# moduloTransceptorRF.net
KiCad netlist of a schematic drawn in Altium Designer
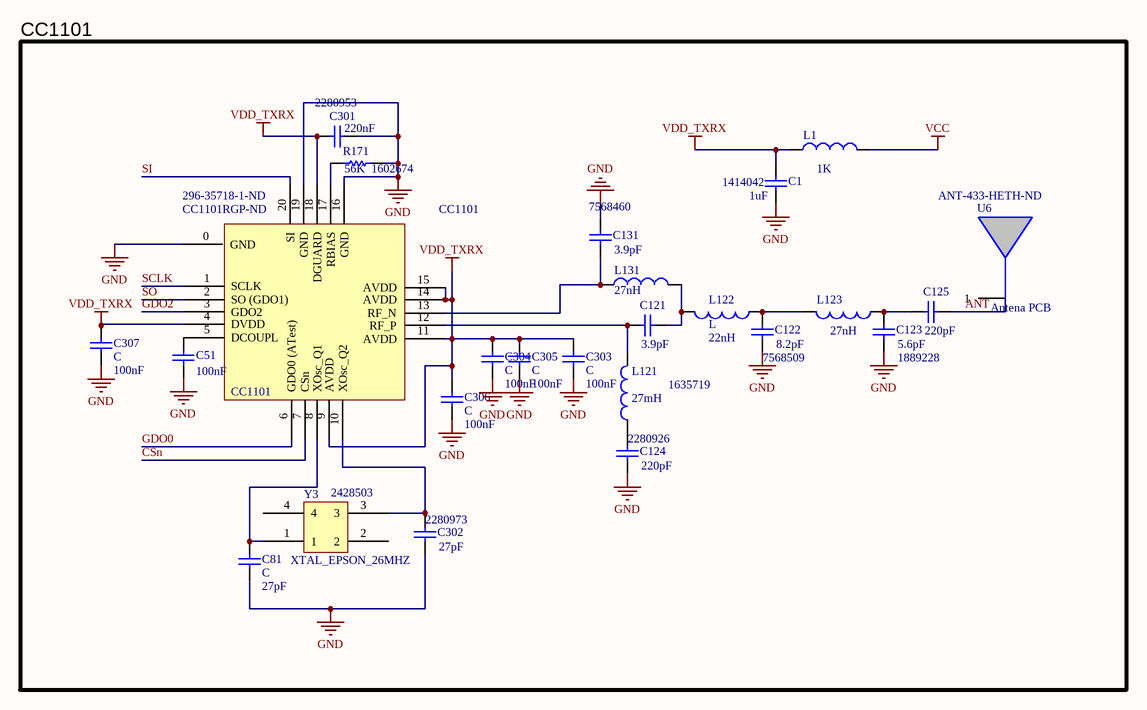
[diagram p0: moduloTransceptorRF.SchDoc]

(export (version "E")
  (design (tool "Eeschema 10.0.6"))
  (components
    (comp (ref "C1")
      (value "1uF")
      (footprint "0805 CAP")
      (description "Capacitor")
      (fields
        (field (name "MANUFACTURER") "Generic Components")
        (field (name "SUPPLIER PART NUMBER 3") "1414042")
        (field (name "Comment") "C")
        (field (name "PUBLISHER") "Altium Hobart Technology Centre")
      )
      (libsource (lib "LSI") (part "C"))
    )
    (comp (ref "C51")
      (value "100nF")
      (footprint "0805 CAP")
      (description "Capacitor")
      (fields
        (field (name "MANUFACTURER") "Generic Components")
        (field (name "Comment") "C")
        (field (name "PUBLISHER") "Altium Hobart Technology Centre")
      )
      (libsource (lib "LSI") (part "C"))
    )
    (comp (ref "C81")
      (value "C")
      (footprint "0805 CAP")
      (description "Capacitor")
      (fields
        (field (name "MANUFACTURER") "Generic Components")
        (field (name "ALTIUM_VALUE") "27pF")
        (field (name "PUBLISHER") "Altium Hobart Technology Centre")
      )
      (libsource (lib "LSI") (part "C"))
    )
    (comp (ref "C121")
      (value "3.9pF")
      (footprint "0805 CAP")
      (description "Capacitor")
      (fields
        (field (name "MANUFACTURER") "Generic Components")
        (field (name "Comment") "C")
        (field (name "PUBLISHER") "Altium Hobart Technology Centre")
      )
      (libsource (lib "LSI") (part "C"))
    )
    (comp (ref "C122")
      (value "8.2pF")
      (footprint "0805 CAP")
      (description "Capacitor")
      (fields
        (field (name "MANUFACTURER") "Generic Components")
        (field (name "SUPPLIER PART NUMBER 1") "7568509")
        (field (name "Comment") "C")
        (field (name "PUBLISHER") "Altium Hobart Technology Centre")
      )
      (libsource (lib "LSI") (part "C"))
    )
    (comp (ref "C123")
      (value "5.6pF")
      (footprint "0805 CAP")
      (description "Capacitor")
      (fields
        (field (name "MANUFACTURER") "Generic Components")
        (field (name "SUPPLIER PART NUMBER 1") "1889228")
        (field (name "Comment") "C")
        (field (name "PUBLISHER") "Altium Hobart Technology Centre")
      )
      (libsource (lib "LSI") (part "C"))
    )
    (comp (ref "C124")
      (value "220pF")
      (footprint "0805 CAP")
      (description "Capacitor")
      (fields
        (field (name "MANUFACTURER") "Generic Components")
        (field (name "SUPPLIER PART NUMBER 1") "2280926")
        (field (name "Comment") "C")
        (field (name "PUBLISHER") "Altium Hobart Technology Centre")
      )
      (libsource (lib "LSI") (part "C"))
    )
    (comp (ref "C125")
      (value "220pF")
      (footprint "0805 CAP")
      (description "Capacitor")
      (fields
        (field (name "MANUFACTURER") "Generic Components")
        (field (name "Comment") "C")
        (field (name "PUBLISHER") "Altium Hobart Technology Centre")
      )
      (libsource (lib "LSI") (part "C"))
    )
    (comp (ref "C131")
      (value "3.9pF")
      (footprint "0805 CAP")
      (description "Capacitor")
      (fields
        (field (name "MANUFACTURER") "Generic Components")
        (field (name "SUPPLIER PART NUMBER 1") "7568460")
        (field (name "Comment") "C")
        (field (name "PUBLISHER") "Altium Hobart Technology Centre")
      )
      (libsource (lib "LSI") (part "C"))
    )
    (comp (ref "C301")
      (value "220nF")
      (footprint "0805 CAP")
      (description "Capacitor")
      (fields
        (field (name "MANUFACTURER") "Generic Components")
        (field (name "SUPPLIER PART NUMBER 1") "2280953")
        (field (name "Comment") "C")
        (field (name "PUBLISHER") "Altium Hobart Technology Centre")
      )
      (libsource (lib "LSI") (part "C"))
    )
    (comp (ref "C302")
      (value "27pF")
      (footprint "0805 CAP")
      (description "Capacitor")
      (fields
        (field (name "MANUFACTURER") "Generic Components")
        (field (name "SUPPLIER PART NUMBER 1") "2280973")
        (field (name "Comment") "C")
        (field (name "PUBLISHER") "Altium Hobart Technology Centre")
      )
      (libsource (lib "LSI") (part "C"))
    )
    (comp (ref "C303")
      (value "C")
      (footprint "0805 CAP")
      (description "Capacitor")
      (fields
        (field (name "MANUFACTURER") "Generic Components")
        (field (name "ALTIUM_VALUE") "100nF")
        (field (name "PUBLISHER") "Altium Hobart Technology Centre")
      )
      (libsource (lib "LSI") (part "C"))
    )
    (comp (ref "C304")
      (value "C")
      (footprint "0805 CAP")
      (description "Capacitor")
      (fields
        (field (name "MANUFACTURER") "Generic Components")
        (field (name "ALTIUM_VALUE") "100nF")
        (field (name "PUBLISHER") "Altium Hobart Technology Centre")
      )
      (libsource (lib "LSI") (part "C"))
    )
    (comp (ref "C305")
      (value "C")
      (footprint "0805 CAP")
      (description "Capacitor")
      (fields
        (field (name "MANUFACTURER") "Generic Components")
        (field (name "ALTIUM_VALUE") "100nF")
        (field (name "PUBLISHER") "Altium Hobart Technology Centre")
      )
      (libsource (lib "LSI") (part "C"))
    )
    (comp (ref "C306")
      (value "C")
      (footprint "0805 CAP")
      (description "Capacitor")
      (fields
        (field (name "MANUFACTURER") "Generic Components")
        (field (name "ALTIUM_VALUE") "100nF")
        (field (name "PUBLISHER") "Altium Hobart Technology Centre")
      )
      (libsource (lib "LSI") (part "C"))
    )
    (comp (ref "C307")
      (value "C")
      (footprint "0805 CAP")
      (description "Capacitor")
      (fields
        (field (name "MANUFACTURER") "Generic Components")
        (field (name "ALTIUM_VALUE") "100nF")
        (field (name "PUBLISHER") "Altium Hobart Technology Centre")
      )
      (libsource (lib "LSI") (part "C"))
    )
    (comp (ref "CC1101")
      (value "CC1101 Transceiver")
      (footprint "CC1101")
      (fields
        (field (name "SUPPLIER PART NUMBER 1") "CC1101RGP-ND")
        (field (name "SUPPLIER PART NUMBER 2") "296-35718-1-ND")
      )
      (libsource (lib "LSI") (part "CC1101 Transceiver"))
    )
    (comp (ref "L1")
      (value "1K")
      (footprint "0805 Ind")
      (description "Inductor")
      (fields
        (field (name "MANUFACTURER") "Generic Components")
        (field (name "Comment") "L")
        (field (name "PUBLISHER") "Altium Hobart Technology Centre")
      )
      (libsource (lib "LSI") (part "L"))
    )
    (comp (ref "L121")
      (value "27mH")
      (footprint "0805 Ind")
      (description "Inductor")
      (fields
        (field (name "MANUFACTURER") "Generic Components")
        (field (name "SUPPLIER PART NUMBER 1") "1635719")
        (field (name "Comment") "L")
        (field (name "PUBLISHER") "Altium Hobart Technology Centre")
      )
      (libsource (lib "LSI") (part "L"))
    )
    (comp (ref "L122")
      (value "L")
      (footprint "0805 Ind")
      (description "Inductor")
      (fields
        (field (name "MANUFACTURER") "Generic Components")
        (field (name "ALTIUM_VALUE") "22nH")
        (field (name "PUBLISHER") "Altium Hobart Technology Centre")
      )
      (libsource (lib "LSI") (part "L"))
    )
    (comp (ref "L123")
      (value "27nH")
      (footprint "0805 Ind")
      (description "Inductor")
      (fields
        (field (name "MANUFACTURER") "Generic Components")
        (field (name "Comment") "L")
        (field (name "PUBLISHER") "Altium Hobart Technology Centre")
      )
      (libsource (lib "LSI") (part "L"))
    )
    (comp (ref "L131")
      (value "27nH")
      (footprint "0805 Ind")
      (description "Inductor")
      (fields
        (field (name "MANUFACTURER") "Generic Components")
        (field (name "Comment") "L")
        (field (name "PUBLISHER") "Altium Hobart Technology Centre")
      )
      (libsource (lib "LSI") (part "L"))
    )
    (comp (ref "R171")
      (value "56K")
      (footprint "0805 RES")
      (description "Resistor")
      (fields
        (field (name "MANUFACTURER") "Generic Components")
        (field (name "SUPPLIER PART NUMBER 1") "1602674")
        (field (name "Comment") "R")
        (field (name "PUBLISHER") "Altium Hobart Technology Centre")
      )
      (libsource (lib "LSI") (part "R"))
    )
    (comp (ref "U6")
      (value "Antena PCB")
      (footprint "ANT-433-HETH")
      (fields
        (field (name "SUPPLIER PART NUMBER 1") "ANT-433-HETH-ND")
        (field (name "PUBLISHER") "Altium Limited")
      )
      (libsource (lib "LSI") (part "Antena PCB"))
    )
    (comp (ref "Y3")
      (value "XTAL_EPSON_26MHZ")
      (footprint "XTAL_EPSON_26MHZ")
      (description "Pin 2 and 4 to ground")
      (fields (field (name "SUPPLIER PART NUMBER 1") "2428503"))
      (libsource (lib "LSI") (part "XTAL_EPSON_26MHZ"))
    )
  )
  (nets
    (net (code "1") (name "/ANT") (class "Default")
      (node (ref "C125") (pin "2") (pinfunction "2_2") (pintype "passive"))
      (node (ref "U6") (pin "1") (pinfunction "1_1") (pintype "passive"))
    )
    (net (code "2") (name "/CSn") (class "Default")
      (node (ref "CC1101") (pin "7") (pinfunction "CSn_7") (pintype "passive"))
    )
    (net (code "3") (name "/GDO0") (class "Default")
      (node (ref "CC1101") (pin "6") (pinfunction "GDO0_(ATest)_6") (pintype "passive"))
    )
    (net (code "4") (name "/GDO2") (class "Default")
      (node (ref "CC1101") (pin "3") (pinfunction "GDO2_3") (pintype "passive"))
    )
    (net (code "5") (name "/SCLK") (class "Default")
      (node (ref "CC1101") (pin "1") (pinfunction "SCLK_1") (pintype "passive"))
    )
    (net (code "6") (name "/SI") (class "Default")
      (node (ref "CC1101") (pin "20") (pinfunction "SI_20") (pintype "passive"))
    )
    (net (code "7") (name "/SO") (class "Default")
      (node (ref "CC1101") (pin "2") (pinfunction "SO_(GDO1)_2") (pintype "passive"))
    )
    (net (code "8") (name "GND") (class "Default")
      (node (ref "C1") (pin "1") (pinfunction "1_1") (pintype "passive"))
      (node (ref "C122") (pin "1") (pinfunction "1_1") (pintype "passive"))
      (node (ref "C123") (pin "1") (pinfunction "1_1") (pintype "passive"))
      (node (ref "C124") (pin "1") (pinfunction "1_1") (pintype "passive"))
      (node (ref "C131") (pin "2") (pinfunction "2_2") (pintype "passive"))
      (node (ref "C301") (pin "2") (pinfunction "2_2") (pintype "passive"))
      (node (ref "C302") (pin "1") (pinfunction "1_1") (pintype "passive"))
      (node (ref "C303") (pin "1") (pinfunction "1_1") (pintype "passive"))
      (node (ref "C304") (pin "1") (pinfunction "1_1") (pintype "passive"))
      (node (ref "C305") (pin "1") (pinfunction "1_1") (pintype "passive"))
      (node (ref "C306") (pin "1") (pinfunction "1_1") (pintype "passive"))
      (node (ref "C307") (pin "1") (pinfunction "1_1") (pintype "passive"))
      (node (ref "C51") (pin "1") (pinfunction "1_1") (pintype "passive"))
      (node (ref "C81") (pin "1") (pinfunction "1_1") (pintype "passive"))
      (node (ref "CC1101") (pin "0") (pinfunction "GND_0") (pintype "passive"))
      (node (ref "CC1101") (pin "16") (pinfunction "GND_16") (pintype "passive"))
      (node (ref "CC1101") (pin "19") (pinfunction "GND_19") (pintype "passive"))
      (node (ref "R171") (pin "1") (pinfunction "1_1") (pintype "passive"))
    )
    (net (code "9") (name "Net-(C121-Pad2)") (class "Default")
      (node (ref "C121") (pin "2") (pinfunction "2_2") (pintype "passive"))
      (node (ref "L122") (pin "2") (pinfunction "2_2") (pintype "passive"))
      (node (ref "L131") (pin "2") (pinfunction "2_2") (pintype "passive"))
    )
    (net (code "10") (name "Net-(C122-Pad2)") (class "Default")
      (node (ref "C122") (pin "2") (pinfunction "2_2") (pintype "passive"))
      (node (ref "L122") (pin "1") (pinfunction "1_1") (pintype "passive"))
      (node (ref "L123") (pin "2") (pinfunction "2_2") (pintype "passive"))
    )
    (net (code "11") (name "Net-(C123-Pad2)") (class "Default")
      (node (ref "C123") (pin "2") (pinfunction "2_2") (pintype "passive"))
      (node (ref "C125") (pin "1") (pinfunction "1_1") (pintype "passive"))
      (node (ref "L123") (pin "1") (pinfunction "1_1") (pintype "passive"))
    )
    (net (code "12") (name "Net-(C124-Pad2)") (class "Default")
      (node (ref "C124") (pin "2") (pinfunction "2_2") (pintype "passive"))
      (node (ref "L121") (pin "1") (pinfunction "1_1") (pintype "passive"))
    )
    (net (code "13") (name "Net-(CC1101-DCOUPL)") (class "Default")
      (node (ref "C51") (pin "2") (pinfunction "2_2") (pintype "passive"))
      (node (ref "CC1101") (pin "5") (pinfunction "DCOUPL_5") (pintype "passive"))
    )
    (net (code "14") (name "Net-(CC1101-RBIAS)") (class "Default")
      (node (ref "CC1101") (pin "17") (pinfunction "RBIAS_17") (pintype "passive"))
      (node (ref "R171") (pin "2") (pinfunction "2_2") (pintype "passive"))
    )
    (net (code "15") (name "Net-(CC1101-RF_N)") (class "Default")
      (node (ref "C131") (pin "1") (pinfunction "1_1") (pintype "passive"))
      (node (ref "CC1101") (pin "13") (pinfunction "RF_N_13") (pintype "passive"))
      (node (ref "L131") (pin "1") (pinfunction "1_1") (pintype "passive"))
    )
    (net (code "16") (name "Net-(CC1101-RF_P)") (class "Default")
      (node (ref "C121") (pin "1") (pinfunction "1_1") (pintype "passive"))
      (node (ref "CC1101") (pin "12") (pinfunction "RF_P_12") (pintype "passive"))
      (node (ref "L121") (pin "2") (pinfunction "2_2") (pintype "passive"))
    )
    (net (code "17") (name "Net-(CC1101-XOsc_Q1)") (class "Default")
      (node (ref "C81") (pin "2") (pinfunction "2_2") (pintype "passive"))
      (node (ref "CC1101") (pin "8") (pinfunction "XOsc_Q1_8") (pintype "passive"))
      (node (ref "Y3") (pin "1") (pinfunction "1_1") (pintype "passive"))
    )
    (net (code "18") (name "Net-(CC1101-XOsc_Q2)") (class "Default")
      (node (ref "C302") (pin "2") (pinfunction "2_2") (pintype "passive"))
      (node (ref "CC1101") (pin "10") (pinfunction "XOsc_Q2_10") (pintype "passive"))
      (node (ref "Y3") (pin "3") (pinfunction "3_3") (pintype "passive"))
    )
    (net (code "19") (name "VCC") (class "Default")
      (node (ref "L1") (pin "2") (pinfunction "2_2") (pintype "passive"))
    )
    (net (code "20") (name "VDD_TXRX") (class "Default")
      (node (ref "C1") (pin "2") (pinfunction "2_2") (pintype "passive"))
      (node (ref "C301") (pin "1") (pinfunction "1_1") (pintype "passive"))
      (node (ref "C303") (pin "2") (pinfunction "2_2") (pintype "passive"))
      (node (ref "C304") (pin "2") (pinfunction "2_2") (pintype "passive"))
      (node (ref "C305") (pin "2") (pinfunction "2_2") (pintype "passive"))
      (node (ref "C306") (pin "2") (pinfunction "2_2") (pintype "passive"))
      (node (ref "C307") (pin "2") (pinfunction "2_2") (pintype "passive"))
      (node (ref "CC1101") (pin "11") (pinfunction "AVDD_11") (pintype "passive"))
      (node (ref "CC1101") (pin "14") (pinfunction "AVDD_14") (pintype "passive"))
      (node (ref "CC1101") (pin "15") (pinfunction "AVDD_15") (pintype "passive"))
      (node (ref "CC1101") (pin "18") (pinfunction "DGUARD_18") (pintype "passive"))
      (node (ref "CC1101") (pin "4") (pinfunction "DVDD_4") (pintype "passive"))
      (node (ref "CC1101") (pin "9") (pinfunction "AVDD_9") (pintype "passive"))
      (node (ref "L1") (pin "1") (pinfunction "1_1") (pintype "passive"))
    )
    (net (code "21") (name "unconnected-(Y3-Pad2)") (class "Default")
      (node (ref "Y3") (pin "2") (pinfunction "2_2") (pintype "passive"))
    )
    (net (code "22") (name "unconnected-(Y3-Pad4)") (class "Default")
      (node (ref "Y3") (pin "4") (pinfunction "4_4") (pintype "passive"))
    )
  )
)
